# MyMultisensors_rev1.net
KiCad netlist of a schematic drawn in EAGLE
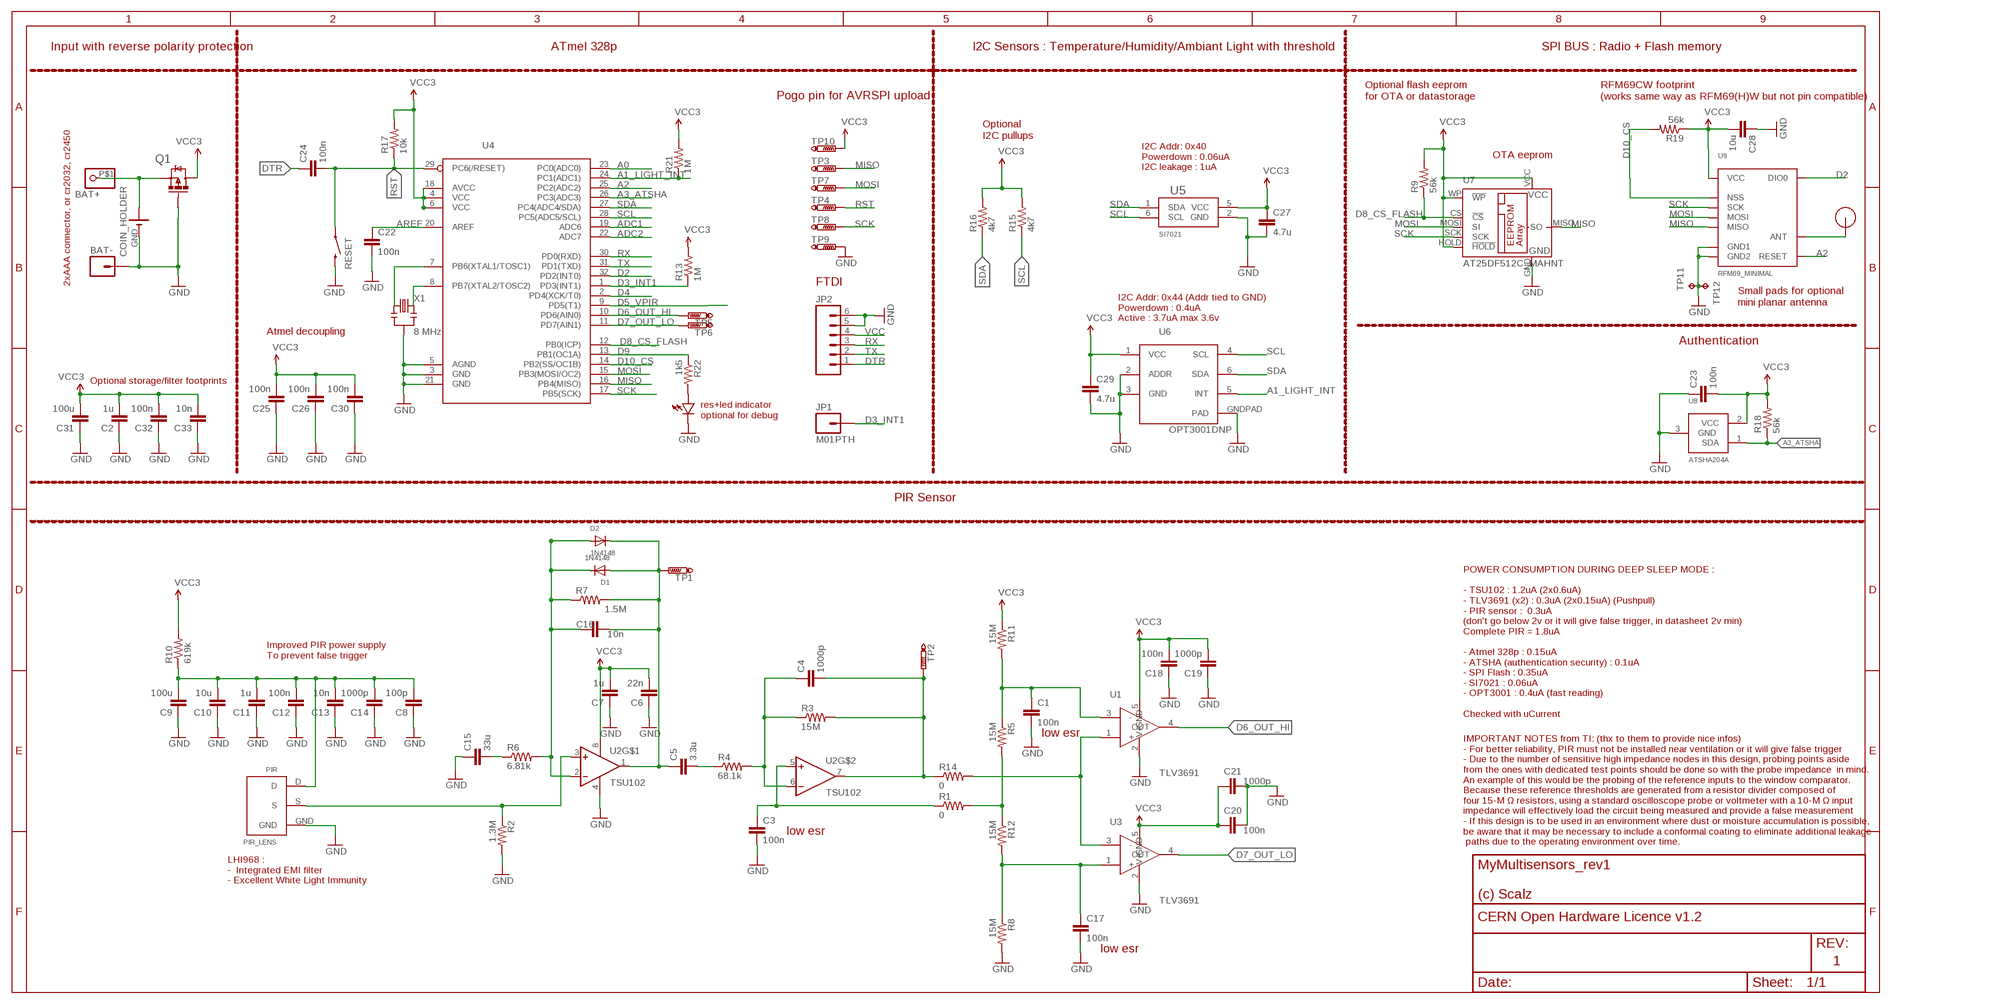
[diagram p0: schematic, sheet 1]

(export (version "E")
  (design (tool "Eeschema 10.0.6"))
  (components
    (comp (ref "ANT")
      (value "RFM12B_ANTENNA")
      (footprint "eagle-import:RFM12B-ANTENNA")
      (libsource (lib "eagle-import") (part "RFM12B_ANTENNA"))
    )
    (comp (ref "BAT+")
      (value "PINHD-1X1TOP")
      (footprint "eagle-import:1X01_ONESIDE")
      (libsource (lib "eagle-import") (part "PINHD-1X1TOP"))
    )
    (comp (ref "BAT-")
      (value "M01PTH")
      (footprint "eagle-import:1X01")
      (libsource (lib "eagle-import") (part "M01PTH"))
    )
    (comp (ref "C1")
      (value "100n")
      (footprint "eagle-import:0603-CAP")
      (libsource (lib "eagle-import") (part "CAP0603-CAP"))
    )
    (comp (ref "C2")
      (value "1u")
      (footprint "eagle-import:0805-CAP")
      (libsource (lib "eagle-import") (part "CAP0805-CAP"))
    )
    (comp (ref "C3")
      (value "100n")
      (footprint "eagle-import:0603-CAP")
      (libsource (lib "eagle-import") (part "CAP0603-CAP"))
    )
    (comp (ref "C4")
      (value "1000p")
      (footprint "eagle-import:0603-CAP")
      (libsource (lib "eagle-import") (part "CAP0603-CAP"))
    )
    (comp (ref "C5")
      (value "3.3u")
      (footprint "eagle-import:0603-CAP")
      (libsource (lib "eagle-import") (part "CAP0603-CAP"))
    )
    (comp (ref "C6")
      (value "22n")
      (footprint "eagle-import:0603-CAP")
      (libsource (lib "eagle-import") (part "CAP0603-CAP"))
    )
    (comp (ref "C7")
      (value "1u")
      (footprint "eagle-import:0603-CAP")
      (libsource (lib "eagle-import") (part "CAP0603-CAP"))
    )
    (comp (ref "C8")
      (value "100p")
      (footprint "eagle-import:0603-CAP")
      (libsource (lib "eagle-import") (part "CAP0603-CAP"))
    )
    (comp (ref "C9")
      (value "100u")
      (footprint "eagle-import:0805-CAP")
      (libsource (lib "eagle-import") (part "CAP0805-CAP"))
    )
    (comp (ref "C10")
      (value "10u")
      (footprint "eagle-import:0805-CAP")
      (libsource (lib "eagle-import") (part "CAP0805-CAP"))
    )
    (comp (ref "C11")
      (value "1u")
      (footprint "eagle-import:0603-CAP")
      (libsource (lib "eagle-import") (part "CAP0603-CAP"))
    )
    (comp (ref "C12")
      (value "100n")
      (footprint "eagle-import:0603-CAP")
      (libsource (lib "eagle-import") (part "CAP0603-CAP"))
    )
    (comp (ref "C13")
      (value "10n")
      (footprint "eagle-import:0603-CAP")
      (libsource (lib "eagle-import") (part "CAP0603-CAP"))
    )
    (comp (ref "C14")
      (value "1000p")
      (footprint "eagle-import:0603-CAP")
      (libsource (lib "eagle-import") (part "CAP0603-CAP"))
    )
    (comp (ref "C15")
      (value "33u")
      (footprint "eagle-import:0805-CAP")
      (libsource (lib "eagle-import") (part "CAP0805-CAP"))
    )
    (comp (ref "C16")
      (value "10n")
      (footprint "eagle-import:0603-CAP")
      (libsource (lib "eagle-import") (part "CAP0603-CAP"))
    )
    (comp (ref "C17")
      (value "100n")
      (footprint "eagle-import:0603-CAP")
      (libsource (lib "eagle-import") (part "CAP0603-CAP"))
    )
    (comp (ref "C18")
      (value "100n")
      (footprint "eagle-import:0603-CAP")
      (libsource (lib "eagle-import") (part "CAP0603-CAP"))
    )
    (comp (ref "C19")
      (value "1000p")
      (footprint "eagle-import:0603-CAP")
      (libsource (lib "eagle-import") (part "CAP0603-CAP"))
    )
    (comp (ref "C20")
      (value "100n")
      (footprint "eagle-import:0603-CAP")
      (libsource (lib "eagle-import") (part "CAP0603-CAP"))
    )
    (comp (ref "C21")
      (value "1000p")
      (footprint "eagle-import:0603-CAP")
      (libsource (lib "eagle-import") (part "CAP0603-CAP"))
    )
    (comp (ref "C22")
      (value "100n")
      (footprint "eagle-import:0603-CAP")
      (libsource (lib "eagle-import") (part "CAP0603-CAP"))
    )
    (comp (ref "C23")
      (value "100n")
      (footprint "eagle-import:0603-CAP")
      (libsource (lib "eagle-import") (part "CAP0603-CAP"))
    )
    (comp (ref "C24")
      (value "100n")
      (footprint "eagle-import:0805-CAP")
      (libsource (lib "eagle-import") (part "CAP0805-CAP"))
    )
    (comp (ref "C25")
      (value "100n")
      (footprint "eagle-import:0603-CAP")
      (libsource (lib "eagle-import") (part "CAP0603-CAP"))
    )
    (comp (ref "C26")
      (value "100n")
      (footprint "eagle-import:0603-CAP")
      (libsource (lib "eagle-import") (part "CAP0603-CAP"))
    )
    (comp (ref "C27")
      (value "4.7u")
      (footprint "eagle-import:0603-CAP")
      (libsource (lib "eagle-import") (part "CAP0603-CAP"))
    )
    (comp (ref "C28")
      (value "10u")
      (footprint "eagle-import:0805-CAP")
      (libsource (lib "eagle-import") (part "CAP0805-CAP"))
    )
    (comp (ref "C29")
      (value "4.7u")
      (footprint "eagle-import:0603-CAP")
      (libsource (lib "eagle-import") (part "CAP0603-CAP"))
    )
    (comp (ref "C30")
      (value "100n")
      (footprint "eagle-import:0603-CAP")
      (libsource (lib "eagle-import") (part "CAP0603-CAP"))
    )
    (comp (ref "C31")
      (value "100u")
      (footprint "eagle-import:0805-CAP")
      (libsource (lib "eagle-import") (part "CAP0805-CAP"))
    )
    (comp (ref "C32")
      (value "100n")
      (footprint "eagle-import:0603-CAP")
      (libsource (lib "eagle-import") (part "CAP0603-CAP"))
    )
    (comp (ref "C33")
      (value "10n")
      (footprint "eagle-import:0603-CAP")
      (libsource (lib "eagle-import") (part "CAP0603-CAP"))
    )
    (comp (ref "COIN_HOLDER")
      (value "CR2450_H_LOWCOSTVERTICAL_WITH_MILL")
      (footprint "eagle-import:CR2450H_LOWCOST2")
      (libsource (lib "eagle-import") (part "CR2450_H_LOWCOSTVERTICAL_WITH_MILL"))
    )
    (comp (ref "D1")
      (value "1N4148")
      (footprint "eagle-import:SOD-123")
      (libsource (lib "eagle-import") (part "DIODESOD-123"))
    )
    (comp (ref "D2")
      (value "1N4148")
      (footprint "eagle-import:SOD-123")
      (libsource (lib "eagle-import") (part "DIODESOD-123"))
    )
    (comp (ref "D3")
      (value "LED0805")
      (footprint "eagle-import:0805-LED")
      (libsource (lib "eagle-import") (part "LED0805"))
    )
    (comp (ref "JP1")
      (value "M01PTH")
      (footprint "eagle-import:1X01")
      (libsource (lib "eagle-import") (part "M01PTH"))
    )
    (comp (ref "JP2")
      (value "M06SIP")
      (footprint "eagle-import:1X06")
      (libsource (lib "eagle-import") (part "M06SIP"))
    )
    (comp (ref "PIR")
      (value "PIR_LENS")
      (footprint "eagle-import:PIR_LENS")
      (libsource (lib "eagle-import") (part "PIR_LENS"))
    )
    (comp (ref "Q1")
      (value "SI2399DS-T1-GE3")
      (footprint "eagle-import:SOT95P237X112-3N")
      (libsource (lib "eagle-import") (part "SI2399DS-T1-GE3"))
    )
    (comp (ref "R1")
      (value "0")
      (footprint "eagle-import:0603-RES")
      (libsource (lib "eagle-import") (part "RESISTOR0603-RES"))
    )
    (comp (ref "R2")
      (value "1.3M")
      (footprint "eagle-import:0603-RES")
      (libsource (lib "eagle-import") (part "RESISTOR0603-RES"))
    )
    (comp (ref "R3")
      (value "15M")
      (footprint "eagle-import:0603-RES")
      (libsource (lib "eagle-import") (part "RESISTOR0603-RES"))
    )
    (comp (ref "R4")
      (value "68.1k")
      (footprint "eagle-import:0603-RES")
      (libsource (lib "eagle-import") (part "RESISTOR0603-RES"))
    )
    (comp (ref "R5")
      (value "15M")
      (footprint "eagle-import:0603-RES")
      (libsource (lib "eagle-import") (part "RESISTOR0603-RES"))
    )
    (comp (ref "R6")
      (value "6.81k")
      (footprint "eagle-import:0603-RES")
      (libsource (lib "eagle-import") (part "RESISTOR0603-RES"))
    )
    (comp (ref "R7")
      (value "1.5M")
      (footprint "eagle-import:0603-RES")
      (libsource (lib "eagle-import") (part "RESISTOR0603-RES"))
    )
    (comp (ref "R8")
      (value "15M")
      (footprint "eagle-import:0603-RES")
      (libsource (lib "eagle-import") (part "RESISTOR0603-RES"))
    )
    (comp (ref "R9")
      (value "56k")
      (footprint "eagle-import:0603-RES")
      (libsource (lib "eagle-import") (part "RESISTOR0603-RES"))
    )
    (comp (ref "R10")
      (value "619k")
      (footprint "eagle-import:0603-RES")
      (libsource (lib "eagle-import") (part "RESISTOR0603-RES"))
    )
    (comp (ref "R11")
      (value "15M")
      (footprint "eagle-import:0603-RES")
      (libsource (lib "eagle-import") (part "RESISTOR0603-RES"))
    )
    (comp (ref "R12")
      (value "15M")
      (footprint "eagle-import:0603-RES")
      (libsource (lib "eagle-import") (part "RESISTOR0603-RES"))
    )
    (comp (ref "R13")
      (value "1M")
      (footprint "eagle-import:0603-RES")
      (libsource (lib "eagle-import") (part "RESISTOR0603-RES"))
    )
    (comp (ref "R14")
      (value "0")
      (footprint "eagle-import:0603-RES")
      (libsource (lib "eagle-import") (part "RESISTOR0603-RES"))
    )
    (comp (ref "R15")
      (value "4k7")
      (footprint "eagle-import:0603-RES")
      (libsource (lib "eagle-import") (part "RESISTOR0603-RES"))
    )
    (comp (ref "R16")
      (value "4k7")
      (footprint "eagle-import:0603-RES")
      (libsource (lib "eagle-import") (part "RESISTOR0603-RES"))
    )
    (comp (ref "R17")
      (value "10k")
      (footprint "eagle-import:0805-RES")
      (libsource (lib "eagle-import") (part "RESISTOR0805-RES"))
    )
    (comp (ref "R18")
      (value "56k")
      (footprint "eagle-import:0603-RES")
      (libsource (lib "eagle-import") (part "RESISTOR0603-RES"))
    )
    (comp (ref "R19")
      (value "56k")
      (footprint "eagle-import:0603-RES")
      (libsource (lib "eagle-import") (part "RESISTOR0603-RES"))
    )
    (comp (ref "R21")
      (value "1M")
      (footprint "eagle-import:0603-RES")
      (libsource (lib "eagle-import") (part "RESISTOR0603-RES"))
    )
    (comp (ref "R22")
      (value "1k5")
      (footprint "eagle-import:0603-RES")
      (libsource (lib "eagle-import") (part "RESISTOR0603-RES"))
    )
    (comp (ref "RESET")
      (value "SWITCH-MOMENTARY-2-SMD-1101NE")
      (footprint "eagle-import:TACTILE-SWITCH-1101NE")
      (libsource (lib "eagle-import") (part "SWITCH-MOMENTARY-2-SMD-1101NE"))
    )
    (comp (ref "TP1")
      (value "PTR1B1,27")
      (footprint "eagle-import:B1,27")
      (libsource (lib "eagle-import") (part "PTR1B1,27"))
    )
    (comp (ref "TP2")
      (value "PTR1B1,27")
      (footprint "eagle-import:B1,27")
      (libsource (lib "eagle-import") (part "PTR1B1,27"))
    )
    (comp (ref "TP3")
      (value "PTR1TP18R")
      (footprint "eagle-import:TP18R")
      (libsource (lib "eagle-import") (part "PTR1TP18R"))
    )
    (comp (ref "TP4")
      (value "PTR1TP18R")
      (footprint "eagle-import:TP18R")
      (libsource (lib "eagle-import") (part "PTR1TP18R"))
    )
    (comp (ref "TP5")
      (value "PTR1B1,27")
      (footprint "eagle-import:B1,27")
      (libsource (lib "eagle-import") (part "PTR1B1,27"))
    )
    (comp (ref "TP6")
      (value "PTR1B1,27")
      (footprint "eagle-import:B1,27")
      (libsource (lib "eagle-import") (part "PTR1B1,27"))
    )
    (comp (ref "TP7")
      (value "PTR1TP18R")
      (footprint "eagle-import:TP18R")
      (libsource (lib "eagle-import") (part "PTR1TP18R"))
    )
    (comp (ref "TP8")
      (value "PTR1TP18R")
      (footprint "eagle-import:TP18R")
      (libsource (lib "eagle-import") (part "PTR1TP18R"))
    )
    (comp (ref "TP9")
      (value "PTR1TP18R")
      (footprint "eagle-import:TP18R")
      (libsource (lib "eagle-import") (part "PTR1TP18R"))
    )
    (comp (ref "TP10")
      (value "PTR1TP18R")
      (footprint "eagle-import:TP18R")
      (libsource (lib "eagle-import") (part "PTR1TP18R"))
    )
    (comp (ref "TP11")
      (value "TPTP10SQ")
      (footprint "eagle-import:TP10SQ")
      (libsource (lib "eagle-import") (part "TPTP10SQ"))
    )
    (comp (ref "TP12")
      (value "TPTP10SQ")
      (footprint "eagle-import:TP10SQ")
      (libsource (lib "eagle-import") (part "TPTP10SQ"))
    )
    (comp (ref "U1")
      (value "TLV3691")
      (footprint "eagle-import:SC70-5")
      (libsource (lib "eagle-import") (part "TLV3691"))
    )
    (comp (ref "U2")
      (value "TSU102")
      (footprint "eagle-import:MINI_SO8")
      (libsource (lib "eagle-import") (part "TSU102"))
    )
    (comp (ref "U3")
      (value "TLV3691")
      (footprint "eagle-import:SC70-5")
      (libsource (lib "eagle-import") (part "TLV3691"))
    )
    (comp (ref "U4")
      (value "ATMega-328")
      (footprint "eagle-import:TQFP32-08")
      (libsource (lib "eagle-import") (part "ATMEGA168/328TQFP32"))
    )
    (comp (ref "U5")
      (value "SI7021")
      (footprint "eagle-import:DFN6")
      (libsource (lib "eagle-import") (part "SI7021"))
    )
    (comp (ref "U6")
      (value "OPT3001DNP")
      (footprint "eagle-import:OPT3001DNP")
      (libsource (lib "eagle-import") (part "OPT3001DNP"))
    )
    (comp (ref "U7")
      (value "AT25DF512C_MAHNT")
      (footprint "eagle-import:AT25DF512C_MAHNT")
      (libsource (lib "eagle-import") (part "AT25DF512C_MAHNT"))
    )
    (comp (ref "U8")
      (value "ATSHA204A")
      (footprint "eagle-import:SOT23")
      (libsource (lib "eagle-import") (part "ATSHA204A"))
    )
    (comp (ref "U9")
      (value "RFM69_MINIMAL")
      (footprint "eagle-import:RFM69CW_MINIMAL")
      (libsource (lib "eagle-import") (part "RFM69_MINIMAL"))
    )
    (comp (ref "X1")
      (value "8 MHz")
      (footprint "eagle-import:RESONATOR-SMD")
      (libsource (lib "eagle-import") (part "RESONATORSMD"))
    )
  )
  (nets
    (net (code "1") (name "/A0") (class "Default")
      (node (ref "U4") (pin "23") (pinfunction "PC0(ADC0)_23") (pintype "bidirectional"))
    )
    (net (code "2") (name "/A1_LIGHT_INT") (class "Default")
      (node (ref "R21") (pin "1") (pinfunction "1_1") (pintype "passive"))
      (node (ref "U4") (pin "24") (pinfunction "PC1(ADC1)_24") (pintype "bidirectional"))
      (node (ref "U6") (pin "5") (pinfunction "INT_5") (pintype "bidirectional"))
    )
    (net (code "3") (name "/A2") (class "Default")
      (node (ref "U4") (pin "25") (pinfunction "PC2(ADC2)_25") (pintype "bidirectional"))
      (node (ref "U9") (pin "RESET") (pinfunction "RESET_RESET") (pintype "bidirectional"))
    )
    (net (code "4") (name "/ADC1") (class "Default")
      (node (ref "U4") (pin "19") (pinfunction "ADC6_19") (pintype "bidirectional"))
    )
    (net (code "5") (name "/ADC2") (class "Default")
      (node (ref "U4") (pin "22") (pinfunction "ADC7_22") (pintype "bidirectional"))
    )
    (net (code "6") (name "/AREF") (class "Default")
      (node (ref "C22") (pin "1") (pinfunction "1_1") (pintype "passive"))
      (node (ref "U4") (pin "20") (pinfunction "AREF_20") (pintype "bidirectional"))
    )
    (net (code "7") (name "/D2") (class "Default")
      (node (ref "U4") (pin "32") (pinfunction "PD2(INT0)_32") (pintype "bidirectional"))
      (node (ref "U9") (pin "DIO0") (pinfunction "DIO0_DIO0") (pintype "open_collector"))
    )
    (net (code "8") (name "/D3_INT1") (class "Default")
      (node (ref "JP1") (pin "1") (pinfunction "1_1") (pintype "passive"))
      (node (ref "R13") (pin "1") (pinfunction "1_1") (pintype "passive"))
      (node (ref "U4") (pin "1") (pinfunction "PD3(INT1)_1") (pintype "bidirectional"))
    )
    (net (code "9") (name "/D4") (class "Default")
      (node (ref "U4") (pin "2") (pinfunction "PD4(XCK/T0)_2") (pintype "bidirectional"))
    )
    (net (code "10") (name "/D5_VPIR") (class "Default")
      (node (ref "U4") (pin "9") (pinfunction "PD5(T1)_9") (pintype "bidirectional"))
    )
    (net (code "11") (name "/D8_CS_FLASH") (class "Default")
      (node (ref "R9") (pin "1") (pinfunction "1_1") (pintype "passive"))
      (node (ref "U4") (pin "12") (pinfunction "PB0(ICP)_12") (pintype "bidirectional"))
      (node (ref "U7") (pin "CS") (pinfunction "~{CS}_CS") (pintype "input"))
    )
    (net (code "12") (name "/D9") (class "Default")
      (node (ref "R22") (pin "1") (pinfunction "1_1") (pintype "passive"))
      (node (ref "U4") (pin "13") (pinfunction "PB1(OC1A)_13") (pintype "bidirectional"))
    )
    (net (code "13") (name "/D10_CS") (class "Default")
      (node (ref "R19") (pin "2") (pinfunction "2_2") (pintype "passive"))
      (node (ref "U4") (pin "14") (pinfunction "PB2(SS/OC1B)_14") (pintype "bidirectional"))
      (node (ref "U9") (pin "NSS") (pinfunction "NSS_NSS") (pintype "input"))
    )
    (net (code "14") (name "/MISO") (class "Default")
      (node (ref "TP3") (pin "TP") (pinfunction "TP_TP") (pintype "input"))
      (node (ref "U4") (pin "16") (pinfunction "PB4(MISO)_16") (pintype "bidirectional"))
      (node (ref "U7") (pin "MISO") (pinfunction "SO_MISO") (pintype "bidirectional"))
      (node (ref "U9") (pin "MISO") (pinfunction "MISO_MISO") (pintype "output"))
    )
    (net (code "15") (name "/MOSI") (class "Default")
      (node (ref "TP7") (pin "TP") (pinfunction "TP_TP") (pintype "input"))
      (node (ref "U4") (pin "15") (pinfunction "PB3(MOSI/OC2)_15") (pintype "bidirectional"))
      (node (ref "U7") (pin "MOSI") (pinfunction "SI_MOSI") (pintype "input"))
      (node (ref "U9") (pin "MOSI") (pinfunction "MOSI_MOSI") (pintype "input"))
    )
    (net (code "16") (name "/N$3") (class "Default")
      (node (ref "PIR") (pin "S") (pinfunction "S_S") (pintype "bidirectional"))
      (node (ref "R2") (pin "1") (pinfunction "1_1") (pintype "passive"))
      (node (ref "U2") (pin "3") (pinfunction "+IN_3") (pintype "input"))
    )
    (net (code "17") (name "/RX") (class "Default")
      (node (ref "JP2") (pin "3") (pinfunction "3_3") (pintype "passive"))
      (node (ref "U4") (pin "30") (pinfunction "PD0(RXD)_30") (pintype "bidirectional"))
    )
    (net (code "18") (name "/SCK") (class "Default")
      (node (ref "TP8") (pin "TP") (pinfunction "TP_TP") (pintype "input"))
      (node (ref "U4") (pin "17") (pinfunction "PB5(SCK)_17") (pintype "bidirectional"))
      (node (ref "U7") (pin "SCK") (pinfunction "SCK_SCK") (pintype "input"))
      (node (ref "U9") (pin "SCK") (pinfunction "SCK_SCK") (pintype "input"))
    )
    (net (code "19") (name "/TX") (class "Default")
      (node (ref "JP2") (pin "2") (pinfunction "2_2") (pintype "passive"))
      (node (ref "U4") (pin "31") (pinfunction "PD1(TXD)_31") (pintype "bidirectional"))
    )
    (net (code "20") (name "A3_ATSHA") (class "Default")
      (node (ref "R18") (pin "1") (pinfunction "1_1") (pintype "passive"))
      (node (ref "U4") (pin "26") (pinfunction "PC3(ADC3)_26") (pintype "bidirectional"))
      (node (ref "U8") (pin "1") (pinfunction "SDA_1") (pintype "bidirectional"))
    )
    (net (code "21") (name "D6_OUT_HI") (class "Default")
      (node (ref "TP5") (pin "TP") (pinfunction "TP_TP") (pintype "input"))
      (node (ref "U1") (pin "4") (pinfunction "OUT_4") (pintype "bidirectional"))
      (node (ref "U4") (pin "10") (pinfunction "PD6(AIN0)_10") (pintype "bidirectional"))
    )
    (net (code "22") (name "D7_OUT_LO") (class "Default")
      (node (ref "TP6") (pin "TP") (pinfunction "TP_TP") (pintype "input"))
      (node (ref "U3") (pin "4") (pinfunction "OUT_4") (pintype "bidirectional"))
      (node (ref "U4") (pin "11") (pinfunction "PD7(AIN1)_11") (pintype "bidirectional"))
    )
    (net (code "23") (name "DTR") (class "Default")
      (node (ref "C24") (pin "1") (pinfunction "1_1") (pintype "passive"))
      (node (ref "JP2") (pin "1") (pinfunction "1_1") (pintype "passive"))
    )
    (net (code "24") (name "GND") (class "Default")
      (node (ref "BAT-") (pin "1") (pinfunction "1_1") (pintype "passive"))
      (node (ref "C1") (pin "2") (pinfunction "2_2") (pintype "passive"))
      (node (ref "C10") (pin "1") (pinfunction "1_1") (pintype "passive"))
      (node (ref "C11") (pin "1") (pinfunction "1_1") (pintype "passive"))
      (node (ref "C12") (pin "1") (pinfunction "1_1") (pintype "passive"))
      (node (ref "C13") (pin "1") (pinfunction "1_1") (pintype "passive"))
      (node (ref "C14") (pin "1") (pinfunction "1_1") (pintype "passive"))
      (node (ref "C15") (pin "1") (pinfunction "1_1") (pintype "passive"))
      (node (ref "C17") (pin "2") (pinfunction "2_2") (pintype "passive"))
      (node (ref "C18") (pin "1") (pinfunction "1_1") (pintype "passive"))
      (node (ref "C19") (pin "1") (pinfunction "1_1") (pintype "passive"))
      (node (ref "C2") (pin "1") (pinfunction "1_1") (pintype "passive"))
      (node (ref "C20") (pin "1") (pinfunction "1_1") (pintype "passive"))
      (node (ref "C21") (pin "1") (pinfunction "1_1") (pintype "passive"))
      (node (ref "C22") (pin "2") (pinfunction "2_2") (pintype "passive"))
      (node (ref "C23") (pin "1") (pinfunction "1_1") (pintype "passive"))
      (node (ref "C25") (pin "1") (pinfunction "1_1") (pintype "passive"))
      (node (ref "C26") (pin "1") (pinfunction "1_1") (pintype "passive"))
      (node (ref "C27") (pin "2") (pinfunction "2_2") (pintype "passive"))
      (node (ref "C28") (pin "1") (pinfunction "1_1") (pintype "passive"))
      (node (ref "C29") (pin "2") (pinfunction "2_2") (pintype "passive"))
      (node (ref "C3") (pin "2") (pinfunction "2_2") (pintype "passive"))
      (node (ref "C30") (pin "1") (pinfunction "1_1") (pintype "passive"))
      (node (ref "C31") (pin "1") (pinfunction "1_1") (pintype "passive"))
      (node (ref "C32") (pin "1") (pinfunction "1_1") (pintype "passive"))
      (node (ref "C33") (pin "1") (pinfunction "1_1") (pintype "passive"))
      (node (ref "C6") (pin "1") (pinfunction "1_1") (pintype "passive"))
      (node (ref "C7") (pin "1") (pinfunction "1_1") (pintype "passive"))
      (node (ref "C8") (pin "1") (pinfunction "1_1") (pintype "passive"))
      (node (ref "C9") (pin "1") (pinfunction "1_1") (pintype "passive"))
      (node (ref "COIN_HOLDER") (pin "GND") (pinfunction "-_GND") (pintype "passive"))
      (node (ref "D3") (pin "MINUS") (pinfunction "MINUS_MINUS") (pintype "passive"))
      (node (ref "JP2") (pin "5") (pinfunction "5_5") (pintype "passive"))
      (node (ref "JP2") (pin "6") (pinfunction "6_6") (pintype "passive"))
      (node (ref "PIR") (pin "GND") (pinfunction "GND_GND") (pintype "bidirectional"))
      (node (ref "Q1") (pin "1") (pinfunction "G_1") (pintype "passive"))
      (node (ref "R2") (pin "2") (pinfunction "2_2") (pintype "passive"))
      (node (ref "R8") (pin "2") (pinfunction "2_2") (pintype "passive"))
      (node (ref "RESET") (pin "P$2") (pinfunction "2_P$2") (pintype "passive"))
      (node (ref "TP11") (pin "TP") (pinfunction "TP_TP") (pintype "input"))
      (node (ref "TP12") (pin "TP") (pinfunction "TP_TP") (pintype "input"))
      (node (ref "TP9") (pin "TP") (pinfunction "TP_TP") (pintype "input"))
      (node (ref "U1") (pin "2") (pinfunction "GND_2") (pintype "bidirectional"))
      (node (ref "U2") (pin "4") (pinfunction "V-_4") (pintype "power_in"))
      (node (ref "U3") (pin "2") (pinfunction "GND_2") (pintype "bidirectional"))
      (node (ref "U4") (pin "21") (pinfunction "GND_21") (pintype "bidirectional"))
      (node (ref "U4") (pin "3") (pinfunction "GND_3") (pintype "bidirectional"))
      (node (ref "U4") (pin "5") (pinfunction "AGND_5") (pintype "bidirectional"))
      (node (ref "U5") (pin "2") (pinfunction "GND_2") (pintype "bidirectional"))
      (node (ref "U6") (pin "2") (pinfunction "ADDR_2") (pintype "bidirectional"))
      (node (ref "U6") (pin "3") (pinfunction "GND_3") (pintype "bidirectional"))
      (node (ref "U6") (pin "GNDPAD") (pinfunction "PAD_GNDPAD") (pintype "bidirectional"))
      (node (ref "U7") (pin "GND") (pinfunction "GND_GND") (pintype "power_in"))
      (node (ref "U8") (pin "3") (pinfunction "GND_3") (pintype "bidirectional"))
      (node (ref "U9") (pin "GND") (pinfunction "GND1_GND") (pintype "power_in"))
      (node (ref "U9") (pin "GND2") (pinfunction "GND2_GND2") (pintype "power_in"))
      (node (ref "X1") (pin "2") (pinfunction "2_2") (pintype "passive"))
    )
    (net (code "25") (name "Net-(ANT-1)") (class "Default")
      (node (ref "ANT") (pin "P$1") (pinfunction "1_P$1") (pintype "bidirectional"))
      (node (ref "U9") (pin "ANT") (pinfunction "ANT_ANT") (pintype "passive"))
    )
    (net (code "26") (name "Net-(BAT+-1)") (class "Default")
      (node (ref "BAT+") (pin "P$1") (pinfunction "1_P$1") (pintype "passive"))
      (node (ref "COIN_HOLDER") (pin "VBAT@1") (pinfunction "+_VBAT@1") (pintype "passive"))
      (node (ref "COIN_HOLDER") (pin "VBAT@2") (pinfunction "+_VBAT@2") (pintype "passive"))
      (node (ref "COIN_HOLDER") (pin "VBAT@3") (pinfunction "+_VBAT@3") (pintype "passive"))
      (node (ref "COIN_HOLDER") (pin "VBAT@4") (pinfunction "+_VBAT@4") (pintype "passive"))
      (node (ref "Q1") (pin "2") (pinfunction "S_2") (pintype "passive"))
    )
    (net (code "27") (name "Net-(C5-Pad2)") (class "Default")
      (node (ref "C5") (pin "2") (pinfunction "2_2") (pintype "passive"))
      (node (ref "R4") (pin "1") (pinfunction "1_1") (pintype "passive"))
    )
    (net (code "28") (name "Net-(C10-Pad2)") (class "Default")
      (node (ref "C10") (pin "2") (pinfunction "2_2") (pintype "passive"))
      (node (ref "C11") (pin "2") (pinfunction "2_2") (pintype "passive"))
      (node (ref "C12") (pin "2") (pinfunction "2_2") (pintype "passive"))
      (node (ref "C13") (pin "2") (pinfunction "2_2") (pintype "passive"))
      (node (ref "C14") (pin "2") (pinfunction "2_2") (pintype "passive"))
      (node (ref "C8") (pin "2") (pinfunction "2_2") (pintype "passive"))
      (node (ref "C9") (pin "2") (pinfunction "2_2") (pintype "passive"))
      (node (ref "PIR") (pin "D") (pinfunction "D_D") (pintype "bidirectional"))
      (node (ref "R10") (pin "1") (pinfunction "1_1") (pintype "passive"))
    )
    (net (code "29") (name "Net-(C15-Pad2)") (class "Default")
      (node (ref "C15") (pin "2") (pinfunction "2_2") (pintype "passive"))
      (node (ref "R6") (pin "1") (pinfunction "1_1") (pintype "passive"))
    )
    (net (code "30") (name "Net-(D3-PadPLUS)") (class "Default")
      (node (ref "D3") (pin "PLUS") (pinfunction "PLUS_PLUS") (pintype "passive"))
      (node (ref "R22") (pin "2") (pinfunction "2_2") (pintype "passive"))
    )
    (net (code "31") (name "Net-(R1-Pad2)") (class "Default")
      (node (ref "R1") (pin "2") (pinfunction "2_2") (pintype "passive"))
      (node (ref "R12") (pin "1") (pinfunction "1_1") (pintype "passive"))
      (node (ref "R5") (pin "2") (pinfunction "2_2") (pintype "passive"))
    )
    (net (code "32") (name "Net-(U1-+)") (class "Default")
      (node (ref "R14") (pin "2") (pinfunction "2_2") (pintype "passive"))
      (node (ref "U1") (pin "1") (pinfunction "+_1") (pintype "bidirectional"))
      (node (ref "U3") (pin "3") (pinfunction "-_3") (pintype "bidirectional"))
    )
    (net (code "33") (name "Net-(U1--)") (class "Default")
      (node (ref "C1") (pin "1") (pinfunction "1_1") (pintype "passive"))
      (node (ref "R11") (pin "2") (pinfunction "2_2") (pintype "passive"))
      (node (ref "R5") (pin "1") (pinfunction "1_1") (pintype "passive"))
      (node (ref "U1") (pin "3") (pinfunction "-_3") (pintype "bidirectional"))
    )
    (net (code "34") (name "Net-(U2A--IN)") (class "Default")
      (node (ref "C16") (pin "1") (pinfunction "1_1") (pintype "passive"))
      (node (ref "D1") (pin "C") (pinfunction "C_C") (pintype "passive"))
      (node (ref "D2") (pin "A") (pinfunction "A_A") (pintype "passive"))
      (node (ref "R6") (pin "2") (pinfunction "2_2") (pintype "passive"))
      (node (ref "R7") (pin "1") (pinfunction "1_1") (pintype "passive"))
      (node (ref "U2") (pin "2") (pinfunction "-IN_2") (pintype "input"))
    )
    (net (code "35") (name "Net-(U2A-OUT)") (class "Default")
      (node (ref "C16") (pin "2") (pinfunction "2_2") (pintype "passive"))
      (node (ref "C5") (pin "1") (pinfunction "1_1") (pintype "passive"))
      (node (ref "D1") (pin "A") (pinfunction "A_A") (pintype "passive"))
      (node (ref "D2") (pin "C") (pinfunction "C_C") (pintype "passive"))
      (node (ref "R7") (pin "2") (pinfunction "2_2") (pintype "passive"))
      (node (ref "TP1") (pin "TP") (pinfunction "TP_TP") (pintype "input"))
      (node (ref "U2") (pin "1") (pinfunction "OUT_1") (pintype "output"))
    )
    (net (code "36") (name "Net-(U2B-+IN)") (class "Default")
      (node (ref "C3") (pin "1") (pinfunction "1_1") (pintype "passive"))
      (node (ref "R1") (pin "1") (pinfunction "1_1") (pintype "passive"))
      (node (ref "U2") (pin "5") (pinfunction "+IN_5") (pintype "input"))
    )
    (net (code "37") (name "Net-(U2B--IN)") (class "Default")
      (node (ref "C4") (pin "1") (pinfunction "1_1") (pintype "passive"))
      (node (ref "R3") (pin "1") (pinfunction "1_1") (pintype "passive"))
      (node (ref "R4") (pin "2") (pinfunction "2_2") (pintype "passive"))
      (node (ref "U2") (pin "6") (pinfunction "-IN_6") (pintype "input"))
    )
    (net (code "38") (name "Net-(U2B-OUT)") (class "Default")
      (node (ref "C4") (pin "2") (pinfunction "2_2") (pintype "passive"))
      (node (ref "R14") (pin "1") (pinfunction "1_1") (pintype "passive"))
      (node (ref "R3") (pin "2") (pinfunction "2_2") (pintype "passive"))
      (node (ref "TP2") (pin "TP") (pinfunction "TP_TP") (pintype "input"))
      (node (ref "U2") (pin "7") (pinfunction "OUT_7") (pintype "output"))
    )
    (net (code "39") (name "Net-(U3-+)") (class "Default")
      (node (ref "C17") (pin "1") (pinfunction "1_1") (pintype "passive"))
      (node (ref "R12") (pin "2") (pinfunction "2_2") (pintype "passive"))
      (node (ref "R8") (pin "1") (pinfunction "1_1") (pintype "passive"))
      (node (ref "U3") (pin "1") (pinfunction "+_1") (pintype "bidirectional"))
    )
    (net (code "40") (name "Net-(U4-PB6(XTAL1{slash}TOSC1))") (class "Default")
      (node (ref "U4") (pin "7") (pinfunction "PB6(XTAL1/TOSC1)_7") (pintype "bidirectional"))
      (node (ref "X1") (pin "1") (pinfunction "1_1") (pintype "passive"))
    )
    (net (code "41") (name "Net-(U4-PB7(XTAL2{slash}TOSC2))") (class "Default")
      (node (ref "U4") (pin "8") (pinfunction "PB7(XTAL2/TOSC2)_8") (pintype "bidirectional"))
      (node (ref "X1") (pin "3") (pinfunction "3_3") (pintype "passive"))
    )
    (net (code "42") (name "RST") (class "Default")
      (node (ref "C24") (pin "2") (pinfunction "2_2") (pintype "passive"))
      (node (ref "R17") (pin "1") (pinfunction "1_1") (pintype "passive"))
      (node (ref "RESET") (pin "P$1") (pinfunction "1_P$1") (pintype "passive"))
      (node (ref "TP4") (pin "TP") (pinfunction "TP_TP") (pintype "input"))
      (node (ref "U4") (pin "29") (pinfunction "PC6(/RESET)_29") (pintype "bidirectional"))
    )
    (net (code "43") (name "SCL") (class "Default")
      (node (ref "R15") (pin "1") (pinfunction "1_1") (pintype "passive"))
      (node (ref "U4") (pin "28") (pinfunction "PC5(ADC5/SCL)_28") (pintype "bidirectional"))
      (node (ref "U5") (pin "6") (pinfunction "SCL_6") (pintype "bidirectional"))
      (node (ref "U6") (pin "4") (pinfunction "SCL_4") (pintype "bidirectional"))
    )
    (net (code "44") (name "SDA") (class "Default")
      (node (ref "R16") (pin "1") (pinfunction "1_1") (pintype "passive"))
      (node (ref "U4") (pin "27") (pinfunction "PC4(ADC4/SDA)_27") (pintype "bidirectional"))
      (node (ref "U5") (pin "1") (pinfunction "SDA_1") (pintype "bidirectional"))
      (node (ref "U6") (pin "6") (pinfunction "SDA_6") (pintype "bidirectional"))
    )
    (net (code "45") (name "VCC3") (class "Default")
      (node (ref "C18") (pin "2") (pinfunction "2_2") (pintype "passive"))
      (node (ref "C19") (pin "2") (pinfunction "2_2") (pintype "passive"))
      (node (ref "C2") (pin "2") (pinfunction "2_2") (pintype "passive"))
      (node (ref "C20") (pin "2") (pinfunction "2_2") (pintype "passive"))
      (node (ref "C21") (pin "2") (pinfunction "2_2") (pintype "passive"))
      (node (ref "C23") (pin "2") (pinfunction "2_2") (pintype "passive"))
      (node (ref "C25") (pin "2") (pinfunction "2_2") (pintype "passive"))
      (node (ref "C26") (pin "2") (pinfunction "2_2") (pintype "passive"))
      (node (ref "C27") (pin "1") (pinfunction "1_1") (pintype "passive"))
      (node (ref "C28") (pin "2") (pinfunction "2_2") (pintype "passive"))
      (node (ref "C29") (pin "1") (pinfunction "1_1") (pintype "passive"))
      (node (ref "C30") (pin "2") (pinfunction "2_2") (pintype "passive"))
      (node (ref "C31") (pin "2") (pinfunction "2_2") (pintype "passive"))
      (node (ref "C32") (pin "2") (pinfunction "2_2") (pintype "passive"))
      (node (ref "C33") (pin "2") (pinfunction "2_2") (pintype "passive"))
      (node (ref "C6") (pin "2") (pinfunction "2_2") (pintype "passive"))
      (node (ref "C7") (pin "2") (pinfunction "2_2") (pintype "passive"))
      (node (ref "JP2") (pin "4") (pinfunction "4_4") (pintype "passive"))
      (node (ref "Q1") (pin "3") (pinfunction "D_3") (pintype "passive"))
      (node (ref "R10") (pin "2") (pinfunction "2_2") (pintype "passive"))
      (node (ref "R11") (pin "1") (pinfunction "1_1") (pintype "passive"))
      (node (ref "R13") (pin "2") (pinfunction "2_2") (pintype "passive"))
      (node (ref "R15") (pin "2") (pinfunction "2_2") (pintype "passive"))
      (node (ref "R16") (pin "2") (pinfunction "2_2") (pintype "passive"))
      (node (ref "R17") (pin "2") (pinfunction "2_2") (pintype "passive"))
      (node (ref "R18") (pin "2") (pinfunction "2_2") (pintype "passive"))
      (node (ref "R19") (pin "1") (pinfunction "1_1") (pintype "passive"))
      (node (ref "R21") (pin "2") (pinfunction "2_2") (pintype "passive"))
      (node (ref "R9") (pin "2") (pinfunction "2_2") (pintype "passive"))
      (node (ref "TP10") (pin "TP") (pinfunction "TP_TP") (pintype "input"))
      (node (ref "U1") (pin "5") (pinfunction "V+_5") (pintype "bidirectional"))
      (node (ref "U2") (pin "8") (pinfunction "V+_8") (pintype "power_in"))
      (node (ref "U3") (pin "5") (pinfunction "V+_5") (pintype "bidirectional"))
      (node (ref "U4") (pin "18") (pinfunction "AVCC_18") (pintype "bidirectional"))
      (node (ref "U4") (pin "4") (pinfunction "VCC_4") (pintype "bidirectional"))
      (node (ref "U4") (pin "6") (pinfunction "VCC_6") (pintype "bidirectional"))
      (node (ref "U5") (pin "5") (pinfunction "VCC_5") (pintype "bidirectional"))
      (node (ref "U6") (pin "1") (pinfunction "VCC_1") (pintype "bidirectional"))
      (node (ref "U7") (pin "HOLD") (pinfunction "~{HOLD}_HOLD") (pintype "input"))
      (node (ref "U7") (pin "VCC") (pinfunction "VCC_VCC") (pintype "power_in"))
      (node (ref "U7") (pin "WP") (pinfunction "~{WP}_WP") (pintype "input"))
      (node (ref "U8") (pin "2") (pinfunction "VCC_2") (pintype "bidirectional"))
      (node (ref "U9") (pin "VDD") (pinfunction "VCC_VDD") (pintype "power_in"))
    )
  )
)
